# Adafruit_RFM_LoRa_Breakout.net
KiCad netlist of a schematic drawn in EAGLE
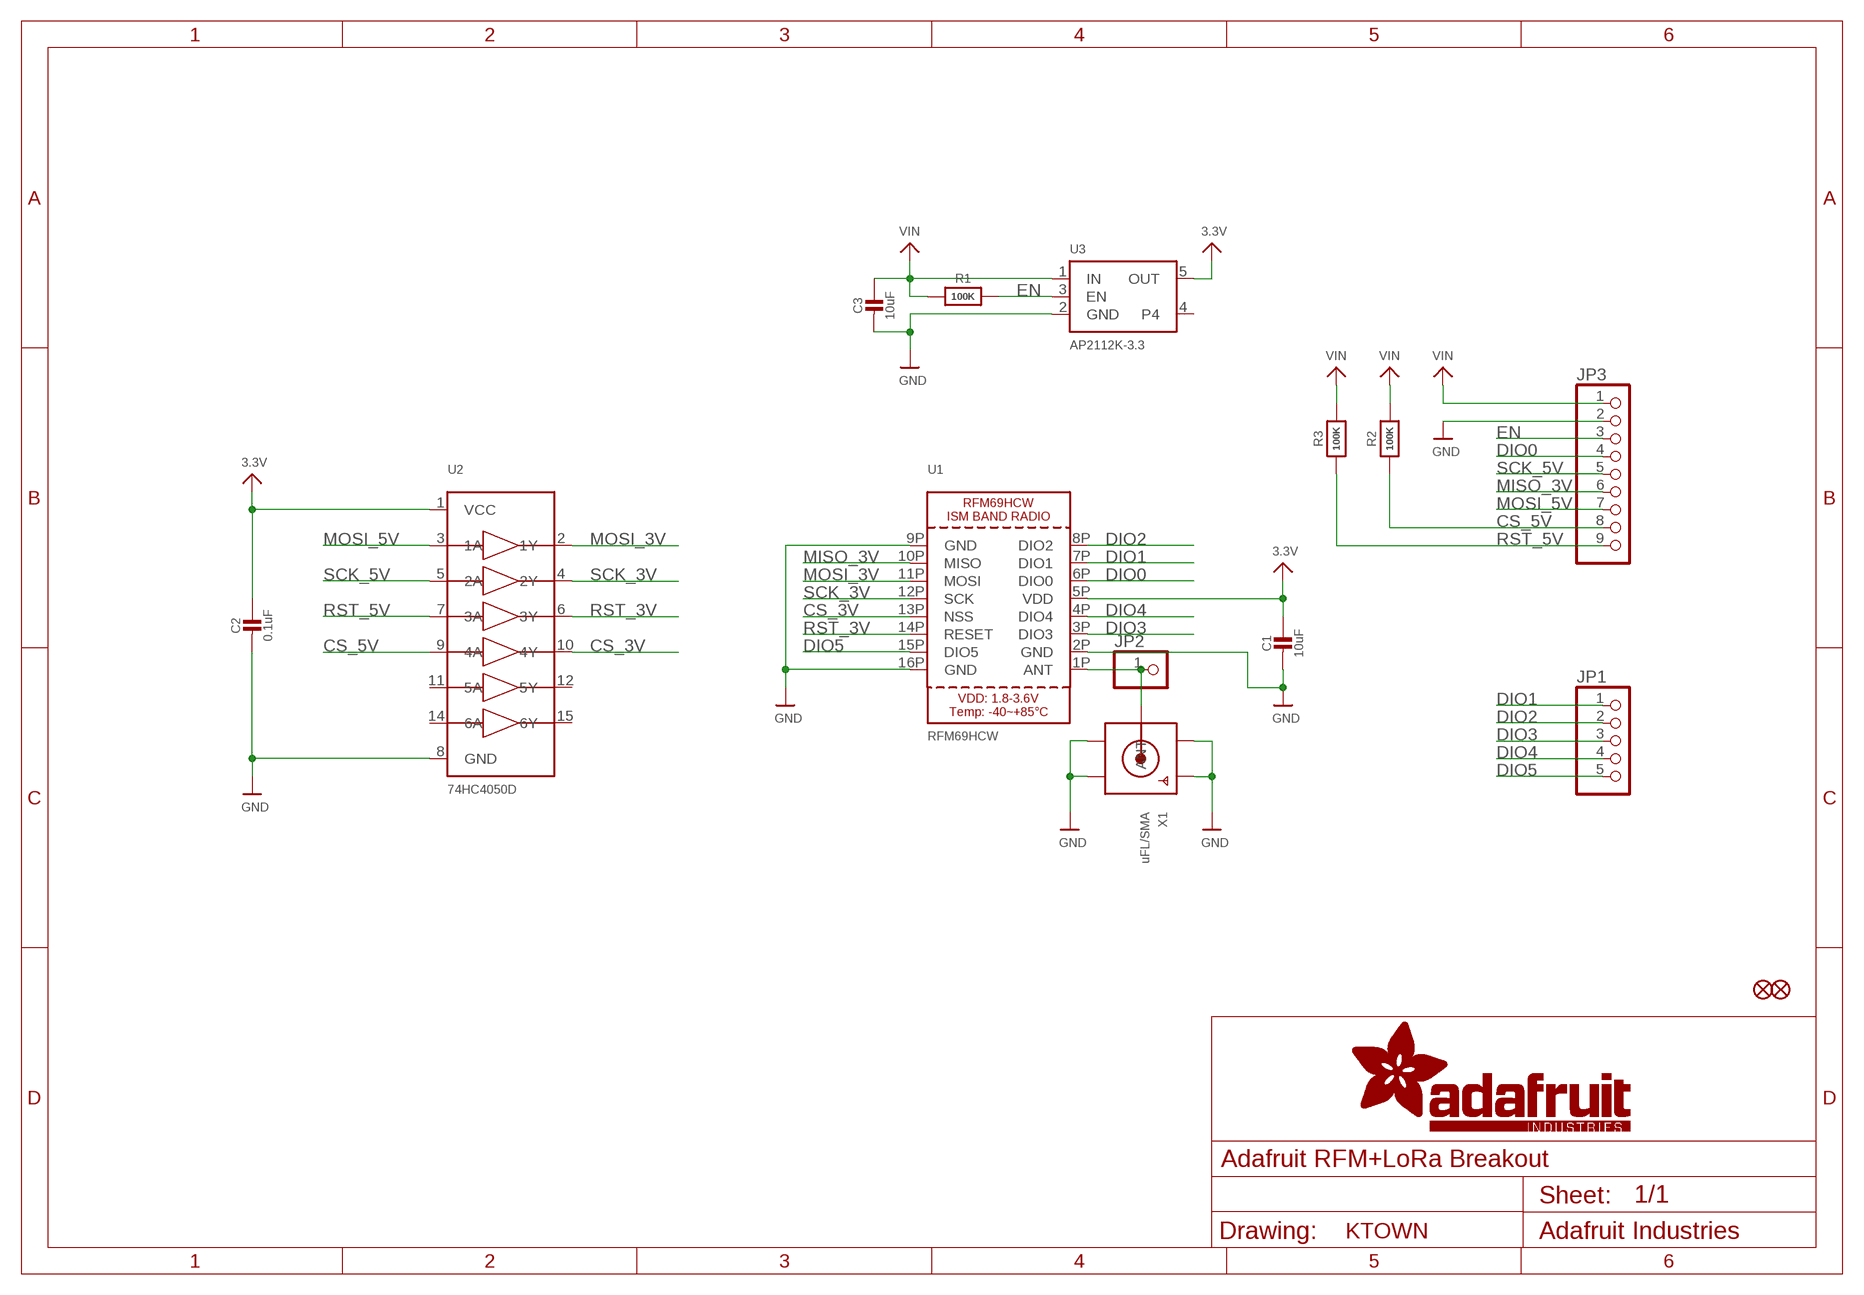
[diagram p0: schematic, sheet 1]

(export (version "E")
  (design (tool "Eeschema 10.0.6"))
  (components
    (comp (ref "C1")
      (value "10uF")
      (footprint "eagle-import:0805-NO")
      (libsource (lib "eagle-import") (part "CAP_CERAMIC0805-NOOUTLINE"))
    )
    (comp (ref "C2")
      (value "0.1uF")
      (footprint "eagle-import:0805-NO")
      (libsource (lib "eagle-import") (part "CAP_CERAMIC0805-NOOUTLINE"))
    )
    (comp (ref "C3")
      (value "10uF")
      (footprint "eagle-import:0805-NO")
      (libsource (lib "eagle-import") (part "CAP_CERAMIC0805-NOOUTLINE"))
    )
    (comp (ref "FID1")
      (value "FIDUCIAL\"\"")
      (footprint "eagle-import:FIDUCIAL_1MM")
      (libsource (lib "eagle-import") (part "FIDUCIAL{dblquote}{dblquote}"))
    )
    (comp (ref "FID2")
      (value "FIDUCIAL\"\"")
      (footprint "eagle-import:FIDUCIAL_1MM")
      (libsource (lib "eagle-import") (part "FIDUCIAL{dblquote}{dblquote}"))
    )
    (comp (ref "JP1")
      (value "HEADER-1X570MIL")
      (footprint "eagle-import:1X05_ROUND_70")
      (libsource (lib "eagle-import") (part "HEADER-1X570MIL"))
    )
    (comp (ref "JP2")
      (value "HEADER-1X1ROUND")
      (footprint "eagle-import:1X01_ROUND")
      (libsource (lib "eagle-import") (part "HEADER-1X1ROUND"))
    )
    (comp (ref "JP3")
      (value "HEADER-1X970MIL")
      (footprint "eagle-import:1X09_ROUND_70")
      (libsource (lib "eagle-import") (part "HEADER-1X970MIL"))
    )
    (comp (ref "R1")
      (value "100K")
      (footprint "eagle-import:0805-NO")
      (libsource (lib "eagle-import") (part "RESISTOR0805_NOOUTLINE"))
    )
    (comp (ref "R2")
      (value "100K")
      (footprint "eagle-import:0805-NO")
      (libsource (lib "eagle-import") (part "RESISTOR0805_NOOUTLINE"))
    )
    (comp (ref "R3")
      (value "100K")
      (footprint "eagle-import:0805-NO")
      (libsource (lib "eagle-import") (part "RESISTOR0805_NOOUTLINE"))
    )
    (comp (ref "U1")
      (value "RFM69HCW")
      (footprint "eagle-import:RFMHCW_SMT")
      (libsource (lib "eagle-import") (part "RFM69HCW_SMT"))
    )
    (comp (ref "U2")
      (value "74HC4050D")
      (footprint "eagle-import:TSSOP16")
      (libsource (lib "eagle-import") (part "74HC4050DTSSOP"))
    )
    (comp (ref "U3")
      (value "AP2112K-3.3")
      (footprint "eagle-import:SOT23-5")
      (libsource (lib "eagle-import") (part "VREG_SOT23-5"))
    )
    (comp (ref "X1")
      (value "uFL/SMA")
      (footprint "eagle-import:SMA_EDGELAUNCH_UFL")
      (libsource (lib "eagle-import") (part "SMACONNECTOR_EDGE_UFL"))
    )
  )
  (nets
    (net (code "1") (name "/CS_3V") (class "Default")
      (node (ref "U1") (pin "13P") (pinfunction "NSS_13P") (pintype "input"))
      (node (ref "U2") (pin "10") (pinfunction "4Y_10") (pintype "bidirectional"))
    )
    (net (code "2") (name "/CS_5V") (class "Default")
      (node (ref "JP3") (pin "8") (pinfunction "8_8") (pintype "passive"))
      (node (ref "R2") (pin "1") (pinfunction "1_1") (pintype "passive"))
      (node (ref "U2") (pin "9") (pinfunction "4A_9") (pintype "bidirectional"))
    )
    (net (code "3") (name "/DIO0") (class "Default")
      (node (ref "JP3") (pin "4") (pinfunction "4_4") (pintype "passive"))
      (node (ref "U1") (pin "6P") (pinfunction "DIO0_6P") (pintype "bidirectional"))
    )
    (net (code "4") (name "/DIO1") (class "Default")
      (node (ref "JP1") (pin "1") (pinfunction "1_1") (pintype "passive"))
      (node (ref "U1") (pin "7P") (pinfunction "DIO1_7P") (pintype "bidirectional"))
    )
    (net (code "5") (name "/DIO2") (class "Default")
      (node (ref "JP1") (pin "2") (pinfunction "2_2") (pintype "passive"))
      (node (ref "U1") (pin "8P") (pinfunction "DIO2_8P") (pintype "bidirectional"))
    )
    (net (code "6") (name "/DIO3") (class "Default")
      (node (ref "JP1") (pin "3") (pinfunction "3_3") (pintype "passive"))
      (node (ref "U1") (pin "3P") (pinfunction "DIO3_3P") (pintype "bidirectional"))
    )
    (net (code "7") (name "/DIO4") (class "Default")
      (node (ref "JP1") (pin "4") (pinfunction "4_4") (pintype "passive"))
      (node (ref "U1") (pin "4P") (pinfunction "DIO4_4P") (pintype "bidirectional"))
    )
    (net (code "8") (name "/DIO5") (class "Default")
      (node (ref "JP1") (pin "5") (pinfunction "5_5") (pintype "passive"))
      (node (ref "U1") (pin "15P") (pinfunction "DIO5_15P") (pintype "bidirectional"))
    )
    (net (code "9") (name "/EN") (class "Default")
      (node (ref "JP3") (pin "3") (pinfunction "3_3") (pintype "passive"))
      (node (ref "R1") (pin "2") (pinfunction "2_2") (pintype "passive"))
      (node (ref "U3") (pin "3") (pinfunction "EN_3") (pintype "input"))
    )
    (net (code "10") (name "/MISO_3V") (class "Default")
      (node (ref "JP3") (pin "6") (pinfunction "6_6") (pintype "passive"))
      (node (ref "U1") (pin "10P") (pinfunction "MISO_10P") (pintype "output"))
    )
    (net (code "11") (name "/MOSI_3V") (class "Default")
      (node (ref "U1") (pin "11P") (pinfunction "MOSI_11P") (pintype "input"))
      (node (ref "U2") (pin "2") (pinfunction "1Y_2") (pintype "bidirectional"))
    )
    (net (code "12") (name "/MOSI_5V") (class "Default")
      (node (ref "JP3") (pin "7") (pinfunction "7_7") (pintype "passive"))
      (node (ref "U2") (pin "3") (pinfunction "1A_3") (pintype "bidirectional"))
    )
    (net (code "13") (name "/RST_3V") (class "Default")
      (node (ref "U1") (pin "14P") (pinfunction "RESET_14P") (pintype "input"))
      (node (ref "U2") (pin "6") (pinfunction "3Y_6") (pintype "bidirectional"))
    )
    (net (code "14") (name "/RST_5V") (class "Default")
      (node (ref "JP3") (pin "9") (pinfunction "9_9") (pintype "passive"))
      (node (ref "R3") (pin "1") (pinfunction "1_1") (pintype "passive"))
      (node (ref "U2") (pin "7") (pinfunction "3A_7") (pintype "bidirectional"))
    )
    (net (code "15") (name "/SCK_3V") (class "Default")
      (node (ref "U1") (pin "12P") (pinfunction "SCK_12P") (pintype "input"))
      (node (ref "U2") (pin "4") (pinfunction "2Y_4") (pintype "bidirectional"))
    )
    (net (code "16") (name "/SCK_5V") (class "Default")
      (node (ref "JP3") (pin "5") (pinfunction "5_5") (pintype "passive"))
      (node (ref "U2") (pin "5") (pinfunction "2A_5") (pintype "bidirectional"))
    )
    (net (code "17") (name "3.3V") (class "Default")
      (node (ref "C1") (pin "1") (pinfunction "1_1") (pintype "passive"))
      (node (ref "C2") (pin "1") (pinfunction "1_1") (pintype "passive"))
      (node (ref "U1") (pin "5P") (pinfunction "VDD_5P") (pintype "power_in"))
      (node (ref "U2") (pin "1") (pinfunction "VCC_1") (pintype "bidirectional"))
      (node (ref "U3") (pin "5") (pinfunction "OUT_5") (pintype "power_in"))
    )
    (net (code "18") (name "GND") (class "Default")
      (node (ref "C1") (pin "2") (pinfunction "2_2") (pintype "passive"))
      (node (ref "C2") (pin "2") (pinfunction "2_2") (pintype "passive"))
      (node (ref "C3") (pin "2") (pinfunction "2_2") (pintype "passive"))
      (node (ref "JP3") (pin "2") (pinfunction "2_2") (pintype "passive"))
      (node (ref "U1") (pin "16P") (pinfunction "GND_16P") (pintype "power_in"))
      (node (ref "U1") (pin "2P") (pinfunction "GND_2P") (pintype "power_in"))
      (node (ref "U1") (pin "9P") (pinfunction "GND_9P") (pintype "power_in"))
      (node (ref "U2") (pin "8") (pinfunction "GND_8") (pintype "bidirectional"))
      (node (ref "U3") (pin "2") (pinfunction "GND_2") (pintype "power_in"))
      (node (ref "X1") (pin "GND@1") (pinfunction "GND1_GND@1") (pintype "power_in"))
      (node (ref "X1") (pin "GND@2") (pinfunction "GND2_GND@2") (pintype "power_in"))
      (node (ref "X1") (pin "GND@3") (pinfunction "GND3_GND@3") (pintype "power_in"))
      (node (ref "X1") (pin "GND@4") (pinfunction "GND4_GND@4") (pintype "power_in"))
    )
    (net (code "19") (name "Net-(U1-ANT)") (class "Default")
      (node (ref "JP2") (pin "1") (pinfunction "1_1") (pintype "passive"))
      (node (ref "U1") (pin "1P") (pinfunction "ANT_1P") (pintype "bidirectional"))
      (node (ref "X1") (pin "P") (pinfunction "ANT_P") (pintype "bidirectional"))
    )
    (net (code "20") (name "VIN") (class "Default")
      (node (ref "C3") (pin "1") (pinfunction "1_1") (pintype "passive"))
      (node (ref "JP3") (pin "1") (pinfunction "1_1") (pintype "passive"))
      (node (ref "R1") (pin "1") (pinfunction "1_1") (pintype "passive"))
      (node (ref "R2") (pin "2") (pinfunction "2_2") (pintype "passive"))
      (node (ref "R3") (pin "2") (pinfunction "2_2") (pintype "passive"))
      (node (ref "U3") (pin "1") (pinfunction "IN_1") (pintype "power_in"))
    )
    (net (code "21") (name "unconnected-(U2-5A-Pad11)") (class "Default")
      (node (ref "U2") (pin "11") (pinfunction "5A_11") (pintype "bidirectional"))
    )
    (net (code "22") (name "unconnected-(U2-5Y-Pad12)") (class "Default")
      (node (ref "U2") (pin "12") (pinfunction "5Y_12") (pintype "bidirectional"))
    )
    (net (code "23") (name "unconnected-(U2-6A-Pad14)") (class "Default")
      (node (ref "U2") (pin "14") (pinfunction "6A_14") (pintype "bidirectional"))
    )
    (net (code "24") (name "unconnected-(U2-6Y-Pad15)") (class "Default")
      (node (ref "U2") (pin "15") (pinfunction "6Y_15") (pintype "bidirectional"))
    )
    (net (code "25") (name "unconnected-(U3-P4-Pad4)") (class "Default")
      (node (ref "U3") (pin "4") (pinfunction "P4_4") (pintype "bidirectional"))
    )
  )
)
